# Valetudo.net
KiCad netlist of a schematic drawn in EAGLE
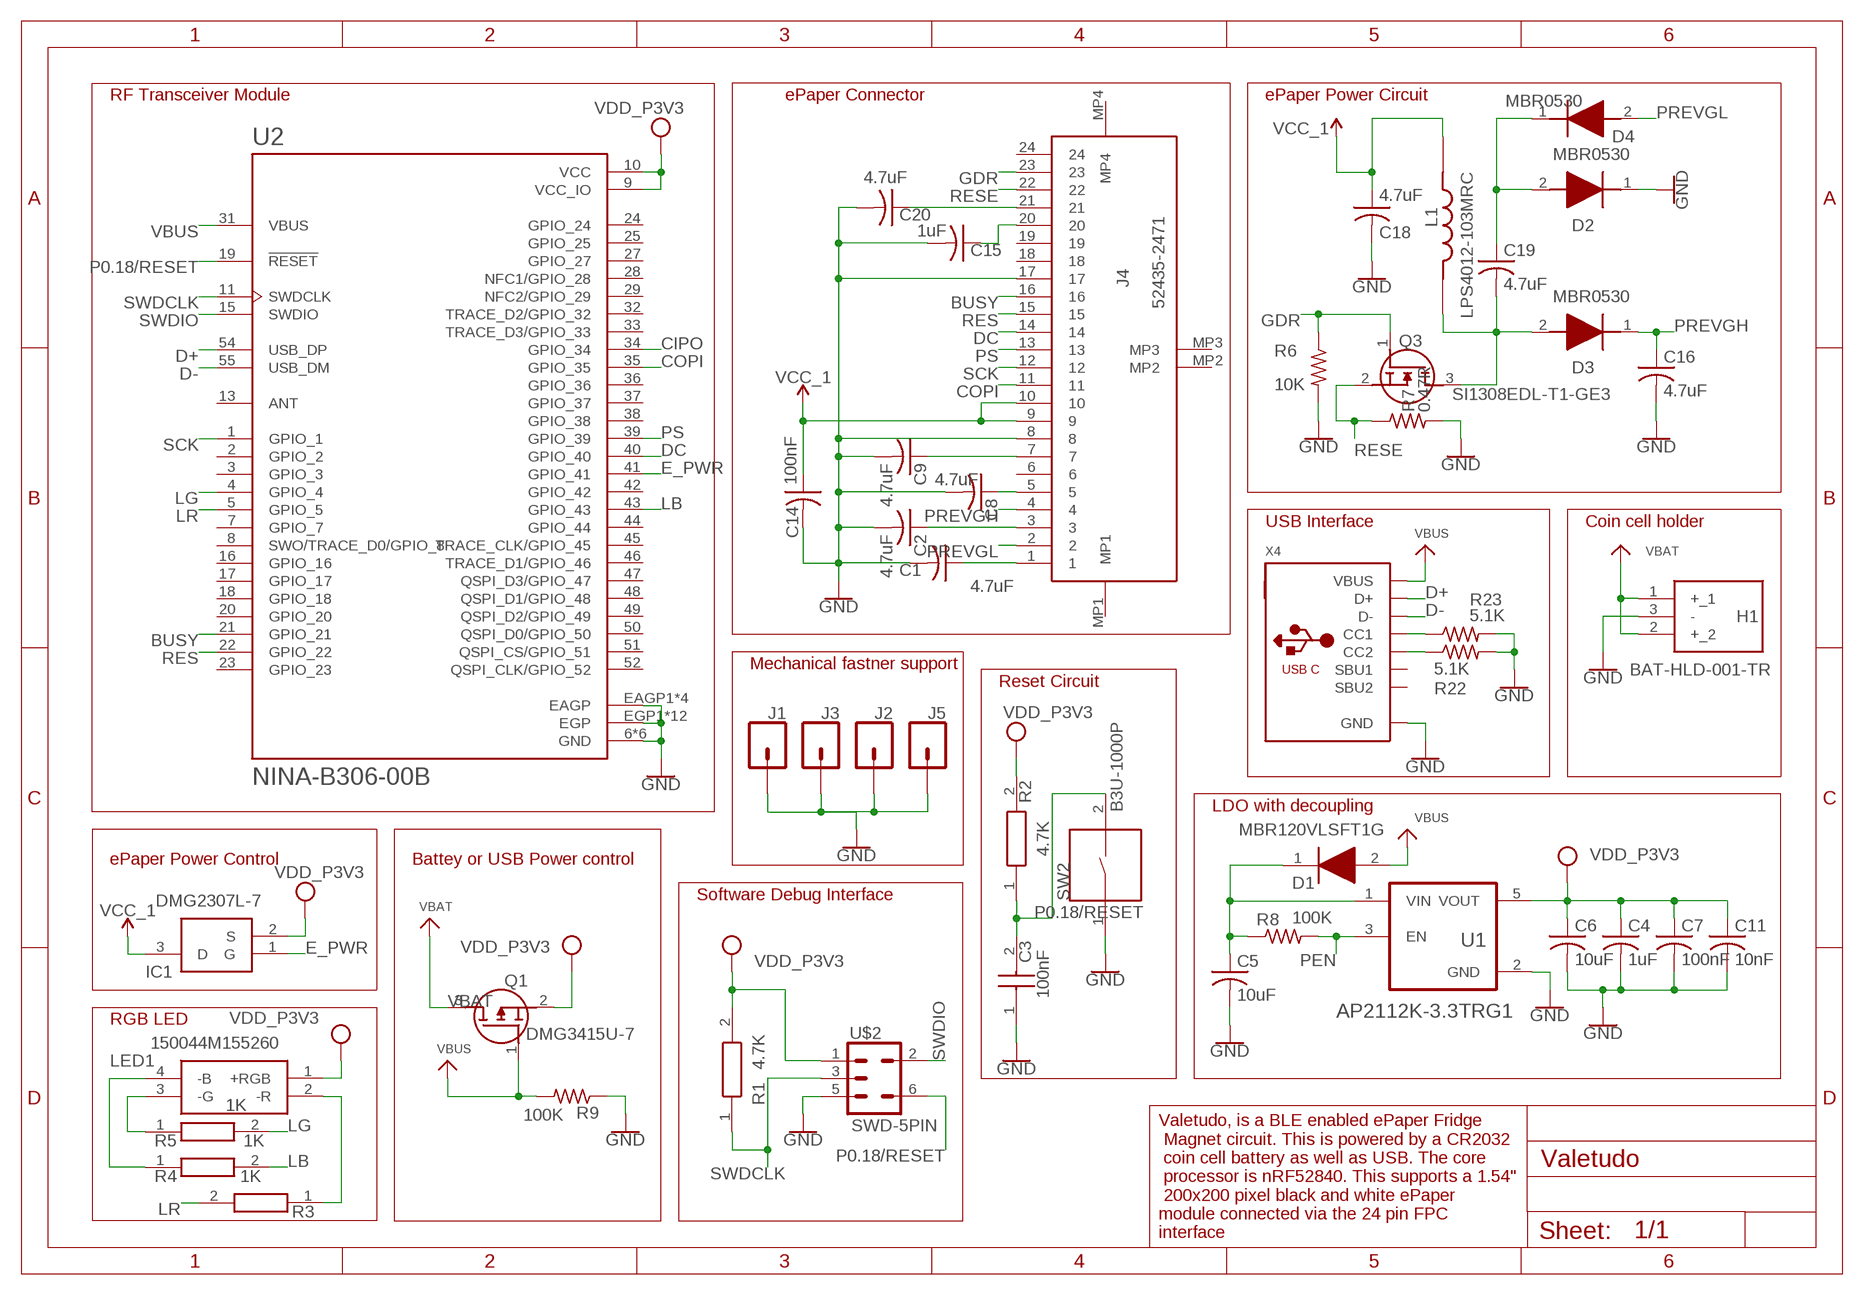
[diagram p0: schematic, sheet 1]

(export (version "E")
  (design (tool "Eeschema 10.0.6"))
  (components
    (comp (ref "C1")
      (value "4.7uF")
      (footprint "eagle-import:C0402")
      (libsource (lib "eagle-import") (part "C-USC0402"))
    )
    (comp (ref "C2")
      (value "4.7uF")
      (footprint "eagle-import:C0402")
      (libsource (lib "eagle-import") (part "C-USC0402"))
    )
    (comp (ref "C3")
      (value "100nF")
      (footprint "eagle-import:CAPC1005X55N")
      (fields
        (field (name "MANUFACTURER_PART_NUMBER") "GJM1555C1H120JB01J")
        (field (name "MOUSER_PART_NUMBER") "81-GJM1555C1H120JB1J")
      )
      (libsource (lib "eagle-import") (part "GJM1555C1H120JB01J"))
    )
    (comp (ref "C4")
      (value "1uF")
      (footprint "eagle-import:C0402")
      (libsource (lib "eagle-import") (part "C-USC0402"))
    )
    (comp (ref "C5")
      (value "10uF")
      (footprint "eagle-import:C0402")
      (libsource (lib "eagle-import") (part "C-USC0402"))
    )
    (comp (ref "C6")
      (value "10uF")
      (footprint "eagle-import:C0402")
      (libsource (lib "eagle-import") (part "C-USC0402"))
    )
    (comp (ref "C7")
      (value "100nF")
      (footprint "eagle-import:C0402")
      (libsource (lib "eagle-import") (part "C-USC0402"))
    )
    (comp (ref "C8")
      (value "4.7uF")
      (footprint "eagle-import:C0402")
      (libsource (lib "eagle-import") (part "C-USC0402"))
    )
    (comp (ref "C9")
      (value "4.7uF")
      (footprint "eagle-import:C0402")
      (libsource (lib "eagle-import") (part "C-USC0402"))
    )
    (comp (ref "C11")
      (value "10nF")
      (footprint "eagle-import:C0402")
      (libsource (lib "eagle-import") (part "C-USC0402"))
    )
    (comp (ref "C14")
      (value "100nF")
      (footprint "eagle-import:C0402")
      (libsource (lib "eagle-import") (part "C-USC0402"))
    )
    (comp (ref "C15")
      (value "1uF")
      (footprint "eagle-import:C0402")
      (libsource (lib "eagle-import") (part "C-USC0402"))
    )
    (comp (ref "C16")
      (value "4.7uF")
      (footprint "eagle-import:C0402")
      (libsource (lib "eagle-import") (part "C-USC0402"))
    )
    (comp (ref "C18")
      (value "4.7uF")
      (footprint "eagle-import:C0402")
      (libsource (lib "eagle-import") (part "C-USC0402"))
    )
    (comp (ref "C19")
      (value "4.7uF")
      (footprint "eagle-import:C0402")
      (libsource (lib "eagle-import") (part "C-USC0402"))
    )
    (comp (ref "C20")
      (value "4.7uF")
      (footprint "eagle-import:C0402")
      (libsource (lib "eagle-import") (part "C-USC0402"))
    )
    (comp (ref "D1")
      (value "MBR120VLSFT1G")
      (footprint "eagle-import:SODFL3616X98N")
      (fields (field (name "MOUSER_PART_NUMBER") "863-MBR120VLSFT1G"))
      (libsource (lib "eagle-import") (part "MBR120VLSFT1G"))
    )
    (comp (ref "D2")
      (value "MBR0530")
      (footprint "eagle-import:SOD3716X135N")
      (fields (field (name "MOUSER_PART_NUMBER") "512-MBR0530"))
      (libsource (lib "eagle-import") (part "MBR0530"))
    )
    (comp (ref "D3")
      (value "MBR0530")
      (footprint "eagle-import:SOD3716X135N")
      (fields (field (name "MOUSER_PART_NUMBER") "512-MBR0530"))
      (libsource (lib "eagle-import") (part "MBR0530"))
    )
    (comp (ref "D4")
      (value "MBR0530")
      (footprint "eagle-import:SOD3716X135N")
      (fields (field (name "MOUSER_PART_NUMBER") "512-MBR0530"))
      (libsource (lib "eagle-import") (part "MBR0530"))
    )
    (comp (ref "H1")
      (value "BAT-HLD-001-TR")
      (footprint "eagle-import:BATHLD001TR")
      (fields (field (name "MOUSER_PART_NUMBER") "712-BAT-HLD-001-TR"))
      (libsource (lib "eagle-import") (part "BAT-HLD-001-TR"))
    )
    (comp (ref "IC1")
      (value "DMG2307L-7")
      (footprint "eagle-import:SOT96P240X110-3N")
      (libsource (lib "eagle-import") (part "DMG2307L-7"))
    )
    (comp (ref "J1")
      (value "CONN_01PTH_2MM")
      (footprint "eagle-import:1X01_2MM")
      (libsource (lib "eagle-import") (part "CONN_01PTH_2MM"))
    )
    (comp (ref "J2")
      (value "CONN_01PTH_2MM")
      (footprint "eagle-import:1X01_2MM")
      (libsource (lib "eagle-import") (part "CONN_01PTH_2MM"))
    )
    (comp (ref "J3")
      (value "CONN_01PTH_2MM")
      (footprint "eagle-import:1X01_2MM")
      (libsource (lib "eagle-import") (part "CONN_01PTH_2MM"))
    )
    (comp (ref "J4")
      (value "52435-2471")
      (footprint "eagle-import:524352471")
      (fields (field (name "MOUSER_PART_NUMBER") "538-52435-2471"))
      (libsource (lib "eagle-import") (part "52435-2471"))
    )
    (comp (ref "J5")
      (value "CONN_01PTH_2MM")
      (footprint "eagle-import:1X01_2MM")
      (libsource (lib "eagle-import") (part "CONN_01PTH_2MM"))
    )
    (comp (ref "L1")
      (value "LPS4012-103MRC")
      (footprint "eagle-import:IND_LPS4012-103MRC")
      (fields (field (name "MF") "Coilcraft"))
      (libsource (lib "eagle-import") (part "LPS4012-103MRC"))
    )
    (comp (ref "LED1")
      (value "150044M155260")
      (footprint "eagle-import:150044M155260")
      (fields (field (name "MOUSER_PART_NUMBER") "710-150044M155260"))
      (libsource (lib "eagle-import") (part "150044M155260"))
    )
    (comp (ref "Q1")
      (value "DMG3415U-7")
      (footprint "eagle-import:SOT96P240X100-3N")
      (fields (field (name "LCSC_PART_NUMBER") "C96616"))
      (libsource (lib "eagle-import") (part "DMG3415U-7"))
    )
    (comp (ref "Q3")
      (value "SI1308EDL-T1-GE3")
      (footprint "eagle-import:SOT65P210X110-3N")
      (fields
        (field (name "MANUFACTURER_PART_NUMBER") "Si1308EDL-T1-GE3")
        (field (name "MOUSER_PART_NUMBER") "78-SI1308EDL-T1-GE3")
      )
      (libsource (lib "eagle-import") (part "SI1308EDL-T1-GE3"))
    )
    (comp (ref "R1")
      (value "4.7K")
      (footprint "eagle-import:RESC1005X40N")
      (fields
        (field (name "ARROW_PART_NUMBER") "CRCW04020000Z0EE")
        (field (name "MOUSER_PART_NUMBER") "71-CRCW04020000Z0EE")
      )
      (libsource (lib "eagle-import") (part "CRCW04020000Z0EE"))
    )
    (comp (ref "R2")
      (value "4.7K")
      (footprint "eagle-import:RESC1005X40N")
      (fields
        (field (name "ARROW_PART_NUMBER") "CRCW04020000Z0EE")
        (field (name "MOUSER_PART_NUMBER") "71-CRCW04020000Z0EE")
      )
      (libsource (lib "eagle-import") (part "CRCW04020000Z0EE"))
    )
    (comp (ref "R3")
      (value "1K")
      (footprint "eagle-import:RESC1005X40N")
      (fields
        (field (name "ARROW_PART_NUMBER") "CRCW04020000Z0EE")
        (field (name "MOUSER_PART_NUMBER") "71-CRCW04020000Z0EE")
      )
      (libsource (lib "eagle-import") (part "CRCW04020000Z0EE"))
    )
    (comp (ref "R4")
      (value "1K")
      (footprint "eagle-import:RESC1005X40N")
      (fields
        (field (name "ARROW_PART_NUMBER") "CRCW04020000Z0EE")
        (field (name "MOUSER_PART_NUMBER") "71-CRCW04020000Z0EE")
      )
      (libsource (lib "eagle-import") (part "CRCW04020000Z0EE"))
    )
    (comp (ref "R5")
      (value "1K")
      (footprint "eagle-import:RESC1005X40N")
      (fields
        (field (name "ARROW_PART_NUMBER") "CRCW04020000Z0EE")
        (field (name "MOUSER_PART_NUMBER") "71-CRCW04020000Z0EE")
      )
      (libsource (lib "eagle-import") (part "CRCW04020000Z0EE"))
    )
    (comp (ref "R6")
      (value "10K")
      (footprint "eagle-import:R0402")
      (libsource (lib "eagle-import") (part "R-US_R0402"))
    )
    (comp (ref "R7")
      (value "0.47R")
      (footprint "eagle-import:R0402")
      (libsource (lib "eagle-import") (part "R-US_R0402"))
    )
    (comp (ref "R8")
      (value "100K")
      (footprint "eagle-import:R0402")
      (libsource (lib "eagle-import") (part "R-US_R0402"))
    )
    (comp (ref "R9")
      (value "100K")
      (footprint "eagle-import:R0402")
      (libsource (lib "eagle-import") (part "R-US_R0402"))
    )
    (comp (ref "R22")
      (value "5.1K")
      (footprint "eagle-import:R0402")
      (libsource (lib "eagle-import") (part "R-US_R0402"))
    )
    (comp (ref "R23")
      (value "5.1K")
      (footprint "eagle-import:R0402")
      (libsource (lib "eagle-import") (part "R-US_R0402"))
    )
    (comp (ref "SW2")
      (value "B3U-1000P")
      (footprint "eagle-import:SW_B3U-1000P")
      (fields (field (name "MF") "Omron"))
      (libsource (lib "eagle-import") (part "B3U-1000P"))
    )
    (comp (ref "U$2")
      (value "SWD-5PIN")
      (footprint "eagle-import:PAD_05_03X2_TP_NO4")
      (libsource (lib "eagle-import") (part "SWD-5PIN"))
    )
    (comp (ref "U1")
      (value "AP2112K-3.3TRG1")
      (footprint "eagle-import:SOT95P285X140-5N")
      (fields (field (name "MF") "Diodes Inc."))
      (libsource (lib "eagle-import") (part "AP2112K-3.3TRG1"))
    )
    (comp (ref "U2")
      (value "NINA-B306-00B")
      (footprint "eagle-import:XCVR_NINA-B306-00B")
      (fields (field (name "MF") "U-Blox"))
      (libsource (lib "eagle-import") (part "NINA-B306-00B"))
    )
    (comp (ref "X4")
      (value "MICROBUILDER_USB_C")
      (footprint "eagle-import:MICROBUILDER_USB_C_CUSB31-CFM2AX-01-X")
      (libsource (lib "eagle-import") (part "MICROBUILDER_USB_C"))
    )
  )
  (nets
    (net (code "1") (name "/BUSY") (class "Default")
      (node (ref "J4") (pin "16") (pinfunction "16_16") (pintype "bidirectional"))
      (node (ref "U2") (pin "21") (pinfunction "GPIO_21_21") (pintype "bidirectional"))
    )
    (net (code "2") (name "/CIPO") (class "Default")
      (node (ref "U2") (pin "34") (pinfunction "GPIO_34_34") (pintype "bidirectional"))
    )
    (net (code "3") (name "/COPI") (class "Default")
      (node (ref "J4") (pin "11") (pinfunction "11_11") (pintype "bidirectional"))
      (node (ref "U2") (pin "35") (pinfunction "GPIO_35_35") (pintype "bidirectional"))
    )
    (net (code "4") (name "/D+") (class "Default")
      (node (ref "U2") (pin "54") (pinfunction "USB_DP_54") (pintype "bidirectional"))
      (node (ref "X4") (pin "A6") (pinfunction "D+_A6") (pintype "bidirectional"))
      (node (ref "X4") (pin "B6") (pinfunction "D+_B6") (pintype "bidirectional"))
    )
    (net (code "5") (name "/D-") (class "Default")
      (node (ref "U2") (pin "55") (pinfunction "USB_DM_55") (pintype "bidirectional"))
      (node (ref "X4") (pin "A7") (pinfunction "D-_A7") (pintype "bidirectional"))
      (node (ref "X4") (pin "B7") (pinfunction "D-_B7") (pintype "bidirectional"))
    )
    (net (code "6") (name "/DC") (class "Default")
      (node (ref "J4") (pin "14") (pinfunction "14_14") (pintype "bidirectional"))
      (node (ref "U2") (pin "40") (pinfunction "GPIO_40_40") (pintype "bidirectional"))
    )
    (net (code "7") (name "/E_PWR") (class "Default")
      (node (ref "IC1") (pin "1") (pinfunction "G_1") (pintype "bidirectional"))
      (node (ref "U2") (pin "41") (pinfunction "GPIO_41_41") (pintype "bidirectional"))
    )
    (net (code "8") (name "/GDR") (class "Default")
      (node (ref "J4") (pin "23") (pinfunction "23_23") (pintype "bidirectional"))
      (node (ref "Q3") (pin "1") (pinfunction "G_1") (pintype "bidirectional"))
      (node (ref "R6") (pin "1") (pinfunction "1_1") (pintype "passive"))
    )
    (net (code "9") (name "/LB") (class "Default")
      (node (ref "R4") (pin "2") (pinfunction "2_2") (pintype "bidirectional"))
      (node (ref "U2") (pin "43") (pinfunction "GPIO_43_43") (pintype "bidirectional"))
    )
    (net (code "10") (name "/LG") (class "Default")
      (node (ref "R5") (pin "2") (pinfunction "2_2") (pintype "bidirectional"))
      (node (ref "U2") (pin "4") (pinfunction "GPIO_4_4") (pintype "bidirectional"))
    )
    (net (code "11") (name "/LR") (class "Default")
      (node (ref "R3") (pin "2") (pinfunction "2_2") (pintype "bidirectional"))
      (node (ref "U2") (pin "5") (pinfunction "GPIO_5_5") (pintype "bidirectional"))
    )
    (net (code "12") (name "/P0.18{slash}RESET") (class "Default")
      (node (ref "C3") (pin "2") (pinfunction "2_2") (pintype "bidirectional"))
      (node (ref "R2") (pin "1") (pinfunction "1_1") (pintype "bidirectional"))
      (node (ref "SW2") (pin "2") (pinfunction "2_2") (pintype "passive"))
      (node (ref "U$2") (pin "6") (pinfunction "6_6") (pintype "bidirectional"))
      (node (ref "U2") (pin "19") (pinfunction "~{RESET}_19") (pintype "bidirectional"))
    )
    (net (code "13") (name "/PEN") (class "Default")
      (node (ref "R8") (pin "2") (pinfunction "2_2") (pintype "passive"))
      (node (ref "U1") (pin "3") (pinfunction "EN_3") (pintype "input"))
    )
    (net (code "14") (name "/PREVGH") (class "Default")
      (node (ref "C16") (pin "1") (pinfunction "1_1") (pintype "passive"))
      (node (ref "D3") (pin "1") (pinfunction "K_1") (pintype "bidirectional"))
      (node (ref "J4") (pin "4") (pinfunction "4_4") (pintype "bidirectional"))
    )
    (net (code "15") (name "/PREVGL") (class "Default")
      (node (ref "D4") (pin "2") (pinfunction "A_2") (pintype "bidirectional"))
      (node (ref "J4") (pin "2") (pinfunction "2_2") (pintype "bidirectional"))
    )
    (net (code "16") (name "/PS") (class "Default")
      (node (ref "J4") (pin "13") (pinfunction "13_13") (pintype "bidirectional"))
      (node (ref "U2") (pin "39") (pinfunction "GPIO_39_39") (pintype "bidirectional"))
    )
    (net (code "17") (name "/RES") (class "Default")
      (node (ref "J4") (pin "15") (pinfunction "15_15") (pintype "bidirectional"))
      (node (ref "U2") (pin "22") (pinfunction "GPIO_22_22") (pintype "bidirectional"))
    )
    (net (code "18") (name "/RESE") (class "Default")
      (node (ref "J4") (pin "22") (pinfunction "22_22") (pintype "bidirectional"))
      (node (ref "Q3") (pin "2") (pinfunction "S_2") (pintype "bidirectional"))
      (node (ref "R7") (pin "1") (pinfunction "1_1") (pintype "passive"))
    )
    (net (code "19") (name "/SCK") (class "Default")
      (node (ref "J4") (pin "12") (pinfunction "12_12") (pintype "bidirectional"))
      (node (ref "U2") (pin "1") (pinfunction "GPIO_1_1") (pintype "bidirectional"))
    )
    (net (code "20") (name "/SWDCLK") (class "Default")
      (node (ref "R1") (pin "1") (pinfunction "1_1") (pintype "bidirectional"))
      (node (ref "U$2") (pin "3") (pinfunction "3_3") (pintype "bidirectional"))
      (node (ref "U2") (pin "11") (pinfunction "SWDCLK_11") (pintype "input"))
    )
    (net (code "21") (name "/SWDIO") (class "Default")
      (node (ref "U$2") (pin "2") (pinfunction "2_2") (pintype "bidirectional"))
      (node (ref "U2") (pin "15") (pinfunction "SWDIO_15") (pintype "bidirectional"))
    )
    (net (code "22") (name "GND") (class "Default")
      (node (ref "C1") (pin "2") (pinfunction "2_2") (pintype "passive"))
      (node (ref "C11") (pin "2") (pinfunction "2_2") (pintype "passive"))
      (node (ref "C14") (pin "2") (pinfunction "2_2") (pintype "passive"))
      (node (ref "C15") (pin "2") (pinfunction "2_2") (pintype "passive"))
      (node (ref "C16") (pin "2") (pinfunction "2_2") (pintype "passive"))
      (node (ref "C18") (pin "2") (pinfunction "2_2") (pintype "passive"))
      (node (ref "C2") (pin "2") (pinfunction "2_2") (pintype "passive"))
      (node (ref "C20") (pin "2") (pinfunction "2_2") (pintype "passive"))
      (node (ref "C3") (pin "1") (pinfunction "1_1") (pintype "bidirectional"))
      (node (ref "C4") (pin "2") (pinfunction "2_2") (pintype "passive"))
      (node (ref "C5") (pin "2") (pinfunction "2_2") (pintype "passive"))
      (node (ref "C6") (pin "2") (pinfunction "2_2") (pintype "passive"))
      (node (ref "C7") (pin "2") (pinfunction "2_2") (pintype "passive"))
      (node (ref "C8") (pin "2") (pinfunction "2_2") (pintype "passive"))
      (node (ref "C9") (pin "2") (pinfunction "2_2") (pintype "passive"))
      (node (ref "D2") (pin "1") (pinfunction "K_1") (pintype "bidirectional"))
      (node (ref "H1") (pin "3") (pinfunction "-_3") (pintype "bidirectional"))
      (node (ref "J1") (pin "1") (pinfunction "1_1") (pintype "passive"))
      (node (ref "J2") (pin "1") (pinfunction "1_1") (pintype "passive"))
      (node (ref "J3") (pin "1") (pinfunction "1_1") (pintype "passive"))
      (node (ref "J4") (pin "17") (pinfunction "17_17") (pintype "bidirectional"))
      (node (ref "J4") (pin "8") (pinfunction "8_8") (pintype "bidirectional"))
      (node (ref "J5") (pin "1") (pinfunction "1_1") (pintype "passive"))
      (node (ref "R22") (pin "2") (pinfunction "2_2") (pintype "passive"))
      (node (ref "R23") (pin "2") (pinfunction "2_2") (pintype "passive"))
      (node (ref "R6") (pin "2") (pinfunction "2_2") (pintype "passive"))
      (node (ref "R7") (pin "2") (pinfunction "2_2") (pintype "passive"))
      (node (ref "R9") (pin "1") (pinfunction "1_1") (pintype "passive"))
      (node (ref "SW2") (pin "1") (pinfunction "1_1") (pintype "passive"))
      (node (ref "U$2") (pin "5") (pinfunction "5_5") (pintype "bidirectional"))
      (node (ref "U1") (pin "2") (pinfunction "GND_2") (pintype "power_in"))
      (node (ref "U2") (pin "12") (pinfunction "GND_12") (pintype "power_in"))
      (node (ref "U2") (pin "14") (pinfunction "GND_14") (pintype "power_in"))
      (node (ref "U2") (pin "26") (pinfunction "GND_26") (pintype "power_in"))
      (node (ref "U2") (pin "30") (pinfunction "GND_30") (pintype "power_in"))
      (node (ref "U2") (pin "53") (pinfunction "GND_53") (pintype "power_in"))
      (node (ref "U2") (pin "6") (pinfunction "GND_6") (pintype "power_in"))
      (node (ref "U2") (pin "EAGP1") (pinfunction "EAGP_EAGP1") (pintype "power_in"))
      (node (ref "U2") (pin "EAGP2") (pinfunction "EAGP_EAGP2") (pintype "power_in"))
      (node (ref "U2") (pin "EAGP3") (pinfunction "EAGP_EAGP3") (pintype "power_in"))
      (node (ref "U2") (pin "EAGP4") (pinfunction "EAGP_EAGP4") (pintype "power_in"))
      (node (ref "U2") (pin "EGP1") (pinfunction "EGP_EGP1") (pintype "power_in"))
      (node (ref "U2") (pin "EGP10") (pinfunction "EGP_EGP10") (pintype "power_in"))
      (node (ref "U2") (pin "EGP11") (pinfunction "EGP_EGP11") (pintype "power_in"))
      (node (ref "U2") (pin "EGP12") (pinfunction "EGP_EGP12") (pintype "power_in"))
      (node (ref "U2") (pin "EGP2") (pinfunction "EGP_EGP2") (pintype "power_in"))
      (node (ref "U2") (pin "EGP3") (pinfunction "EGP_EGP3") (pintype "power_in"))
      (node (ref "U2") (pin "EGP4") (pinfunction "EGP_EGP4") (pintype "power_in"))
      (node (ref "U2") (pin "EGP5") (pinfunction "EGP_EGP5") (pintype "power_in"))
      (node (ref "U2") (pin "EGP6") (pinfunction "EGP_EGP6") (pintype "power_in"))
      (node (ref "U2") (pin "EGP7") (pinfunction "EGP_EGP7") (pintype "power_in"))
      (node (ref "U2") (pin "EGP8") (pinfunction "EGP_EGP8") (pintype "power_in"))
      (node (ref "U2") (pin "EGP9") (pinfunction "EGP_EGP9") (pintype "power_in"))
      (node (ref "X4") (pin "A1B12") (pinfunction "GND_A1B12") (pintype "power_in"))
      (node (ref "X4") (pin "B1A12") (pinfunction "GND_B1A12") (pintype "power_in"))
    )
    (net (code "23") (name "Net-(C1-Pad1)") (class "Default")
      (node (ref "C1") (pin "1") (pinfunction "1_1") (pintype "passive"))
      (node (ref "J4") (pin "1") (pinfunction "1_1") (pintype "bidirectional"))
    )
    (net (code "24") (name "Net-(C2-Pad1)") (class "Default")
      (node (ref "C2") (pin "1") (pinfunction "1_1") (pintype "passive"))
      (node (ref "J4") (pin "3") (pinfunction "3_3") (pintype "bidirectional"))
    )
    (net (code "25") (name "Net-(C8-Pad1)") (class "Default")
      (node (ref "C8") (pin "1") (pinfunction "1_1") (pintype "passive"))
      (node (ref "J4") (pin "5") (pinfunction "5_5") (pintype "bidirectional"))
    )
    (net (code "26") (name "Net-(C9-Pad1)") (class "Default")
      (node (ref "C9") (pin "1") (pinfunction "1_1") (pintype "passive"))
      (node (ref "J4") (pin "7") (pinfunction "7_7") (pintype "bidirectional"))
    )
    (net (code "27") (name "Net-(C15-Pad1)") (class "Default")
      (node (ref "C15") (pin "1") (pinfunction "1_1") (pintype "passive"))
      (node (ref "J4") (pin "20") (pinfunction "20_20") (pintype "bidirectional"))
    )
    (net (code "28") (name "Net-(C20-Pad1)") (class "Default")
      (node (ref "C20") (pin "1") (pinfunction "1_1") (pintype "passive"))
      (node (ref "J4") (pin "21") (pinfunction "21_21") (pintype "bidirectional"))
    )
    (net (code "29") (name "Net-(D1-K)") (class "Default")
      (node (ref "C5") (pin "1") (pinfunction "1_1") (pintype "passive"))
      (node (ref "D1") (pin "1") (pinfunction "K_1") (pintype "bidirectional"))
      (node (ref "R8") (pin "1") (pinfunction "1_1") (pintype "passive"))
      (node (ref "U1") (pin "1") (pinfunction "VIN_1") (pintype "power_in"))
    )
    (net (code "30") (name "Net-(D2-A)") (class "Default")
      (node (ref "C19") (pin "1") (pinfunction "1_1") (pintype "passive"))
      (node (ref "D2") (pin "2") (pinfunction "A_2") (pintype "bidirectional"))
      (node (ref "D4") (pin "1") (pinfunction "K_1") (pintype "bidirectional"))
    )
    (net (code "31") (name "Net-(D3-A)") (class "Default")
      (node (ref "C19") (pin "2") (pinfunction "2_2") (pintype "passive"))
      (node (ref "D3") (pin "2") (pinfunction "A_2") (pintype "bidirectional"))
      (node (ref "L1") (pin "2") (pinfunction "2_2") (pintype "passive"))
      (node (ref "Q3") (pin "3") (pinfunction "D_3") (pintype "bidirectional"))
    )
    (net (code "32") (name "Net-(LED1--B)") (class "Default")
      (node (ref "LED1") (pin "4") (pinfunction "-B_4") (pintype "bidirectional"))
      (node (ref "R4") (pin "1") (pinfunction "1_1") (pintype "bidirectional"))
    )
    (net (code "33") (name "Net-(LED1--G)") (class "Default")
      (node (ref "LED1") (pin "3") (pinfunction "-G_3") (pintype "bidirectional"))
      (node (ref "R5") (pin "1") (pinfunction "1_1") (pintype "bidirectional"))
    )
    (net (code "34") (name "Net-(LED1--R)") (class "Default")
      (node (ref "LED1") (pin "2") (pinfunction "-R_2") (pintype "bidirectional"))
      (node (ref "R3") (pin "1") (pinfunction "1_1") (pintype "bidirectional"))
    )
    (net (code "35") (name "Net-(X4-CC1)") (class "Default")
      (node (ref "R23") (pin "1") (pinfunction "1_1") (pintype "passive"))
      (node (ref "X4") (pin "A5") (pinfunction "CC1_A5") (pintype "bidirectional"))
    )
    (net (code "36") (name "Net-(X4-CC2)") (class "Default")
      (node (ref "R22") (pin "1") (pinfunction "1_1") (pintype "passive"))
      (node (ref "X4") (pin "B5") (pinfunction "CC2_B5") (pintype "bidirectional"))
    )
    (net (code "37") (name "VBAT") (class "Default")
      (node (ref "H1") (pin "1") (pinfunction "+_1_1") (pintype "bidirectional"))
      (node (ref "H1") (pin "2") (pinfunction "+_2_2") (pintype "bidirectional"))
      (node (ref "Q1") (pin "3") (pinfunction "D_3") (pintype "bidirectional"))
    )
    (net (code "38") (name "VBUS") (class "Default")
      (node (ref "D1") (pin "2") (pinfunction "A_2") (pintype "bidirectional"))
      (node (ref "Q1") (pin "1") (pinfunction "G_1") (pintype "bidirectional"))
      (node (ref "R9") (pin "2") (pinfunction "2_2") (pintype "passive"))
      (node (ref "U2") (pin "31") (pinfunction "VBUS_31") (pintype "input"))
      (node (ref "X4") (pin "A4B9") (pinfunction "VBUS_A4B9") (pintype "power_in"))
      (node (ref "X4") (pin "B4A9") (pinfunction "VBUS_B4A9") (pintype "power_in"))
    )
    (net (code "39") (name "VCC_1") (class "Default")
      (node (ref "C14") (pin "1") (pinfunction "1_1") (pintype "passive"))
      (node (ref "C18") (pin "1") (pinfunction "1_1") (pintype "passive"))
      (node (ref "IC1") (pin "3") (pinfunction "D_3") (pintype "bidirectional"))
      (node (ref "J4") (pin "10") (pinfunction "10_10") (pintype "bidirectional"))
      (node (ref "J4") (pin "9") (pinfunction "9_9") (pintype "bidirectional"))
      (node (ref "L1") (pin "1") (pinfunction "1_1") (pintype "passive"))
    )
    (net (code "40") (name "VDD_P3V3") (class "Default")
      (node (ref "C11") (pin "1") (pinfunction "1_1") (pintype "passive"))
      (node (ref "C4") (pin "1") (pinfunction "1_1") (pintype "passive"))
      (node (ref "C6") (pin "1") (pinfunction "1_1") (pintype "passive"))
      (node (ref "C7") (pin "1") (pinfunction "1_1") (pintype "passive"))
      (node (ref "IC1") (pin "2") (pinfunction "S_2") (pintype "bidirectional"))
      (node (ref "LED1") (pin "1") (pinfunction "+RGB_1") (pintype "bidirectional"))
      (node (ref "Q1") (pin "2") (pinfunction "S_2") (pintype "bidirectional"))
      (node (ref "R1") (pin "2") (pinfunction "2_2") (pintype "bidirectional"))
      (node (ref "R2") (pin "2") (pinfunction "2_2") (pintype "bidirectional"))
      (node (ref "U$2") (pin "1") (pinfunction "1_1") (pintype "bidirectional"))
      (node (ref "U1") (pin "5") (pinfunction "VOUT_5") (pintype "power_in"))
      (node (ref "U2") (pin "10") (pinfunction "VCC_10") (pintype "power_in"))
      (node (ref "U2") (pin "9") (pinfunction "VCC_IO_9") (pintype "power_in"))
    )
    (net (code "41") (name "unconnected-(J4-Pad6)") (class "Default")
      (node (ref "J4") (pin "6") (pinfunction "6_6") (pintype "bidirectional"))
    )
    (net (code "42") (name "unconnected-(J4-Pad18)") (class "Default")
      (node (ref "J4") (pin "18") (pinfunction "18_18") (pintype "bidirectional"))
    )
    (net (code "43") (name "unconnected-(J4-Pad19)") (class "Default")
      (node (ref "J4") (pin "19") (pinfunction "19_19") (pintype "bidirectional"))
    )
    (net (code "44") (name "unconnected-(J4-Pad24)") (class "Default")
      (node (ref "J4") (pin "24") (pinfunction "24_24") (pintype "bidirectional"))
    )
    (net (code "45") (name "unconnected-(J4-PadMP1)") (class "Default")
      (node (ref "J4") (pin "MP1") (pinfunction "MP1_MP1") (pintype "bidirectional"))
    )
    (net (code "46") (name "unconnected-(J4-PadMP2)") (class "Default")
      (node (ref "J4") (pin "MP2") (pinfunction "MP2_MP2") (pintype "bidirectional"))
    )
    (net (code "47") (name "unconnected-(J4-PadMP3)") (class "Default")
      (node (ref "J4") (pin "MP3") (pinfunction "MP3_MP3") (pintype "bidirectional"))
    )
    (net (code "48") (name "unconnected-(J4-PadMP4)") (class "Default")
      (node (ref "J4") (pin "MP4") (pinfunction "MP4_MP4") (pintype "bidirectional"))
    )
    (net (code "49") (name "unconnected-(U2-ANT-Pad13)") (class "Default")
      (node (ref "U2") (pin "13") (pinfunction "ANT_13") (pintype "bidirectional"))
    )
    (net (code "50") (name "unconnected-(U2-GPIO_2-Pad2)") (class "Default")
      (node (ref "U2") (pin "2") (pinfunction "GPIO_2_2") (pintype "bidirectional"))
    )
    (net (code "51") (name "unconnected-(U2-GPIO_3-Pad3)") (class "Default")
      (node (ref "U2") (pin "3") (pinfunction "GPIO_3_3") (pintype "bidirectional"))
    )
    (net (code "52") (name "unconnected-(U2-GPIO_7-Pad7)") (class "Default")
      (node (ref "U2") (pin "7") (pinfunction "GPIO_7_7") (pintype "bidirectional"))
    )
    (net (code "53") (name "unconnected-(U2-GPIO_16-Pad16)") (class "Default")
      (node (ref "U2") (pin "16") (pinfunction "GPIO_16_16") (pintype "bidirectional"))
    )
    (net (code "54") (name "unconnected-(U2-GPIO_17-Pad17)") (class "Default")
      (node (ref "U2") (pin "17") (pinfunction "GPIO_17_17") (pintype "bidirectional"))
    )
    (net (code "55") (name "unconnected-(U2-GPIO_18-Pad18)") (class "Default")
      (node (ref "U2") (pin "18") (pinfunction "GPIO_18_18") (pintype "bidirectional"))
    )
    (net (code "56") (name "unconnected-(U2-GPIO_20-Pad20)") (class "Default")
      (node (ref "U2") (pin "20") (pinfunction "GPIO_20_20") (pintype "bidirectional"))
    )
    (net (code "57") (name "unconnected-(U2-GPIO_23-Pad23)") (class "Default")
      (node (ref "U2") (pin "23") (pinfunction "GPIO_23_23") (pintype "bidirectional"))
    )
    (net (code "58") (name "unconnected-(U2-GPIO_24-Pad24)") (class "Default")
      (node (ref "U2") (pin "24") (pinfunction "GPIO_24_24") (pintype "bidirectional"))
    )
    (net (code "59") (name "unconnected-(U2-GPIO_25-Pad25)") (class "Default")
      (node (ref "U2") (pin "25") (pinfunction "GPIO_25_25") (pintype "bidirectional"))
    )
    (net (code "60") (name "unconnected-(U2-GPIO_27-Pad27)") (class "Default")
      (node (ref "U2") (pin "27") (pinfunction "GPIO_27_27") (pintype "bidirectional"))
    )
    (net (code "61") (name "unconnected-(U2-GPIO_36-Pad36)") (class "Default")
      (node (ref "U2") (pin "36") (pinfunction "GPIO_36_36") (pintype "bidirectional"))
    )
    (net (code "62") (name "unconnected-(U2-GPIO_37-Pad37)") (class "Default")
      (node (ref "U2") (pin "37") (pinfunction "GPIO_37_37") (pintype "bidirectional"))
    )
    (net (code "63") (name "unconnected-(U2-GPIO_38-Pad38)") (class "Default")
      (node (ref "U2") (pin "38") (pinfunction "GPIO_38_38") (pintype "bidirectional"))
    )
    (net (code "64") (name "unconnected-(U2-GPIO_42-Pad42)") (class "Default")
      (node (ref "U2") (pin "42") (pinfunction "GPIO_42_42") (pintype "bidirectional"))
    )
    (net (code "65") (name "unconnected-(U2-GPIO_44-Pad44)") (class "Default")
      (node (ref "U2") (pin "44") (pinfunction "GPIO_44_44") (pintype "bidirectional"))
    )
    (net (code "66") (name "unconnected-(U2-NFC1{slash}GPIO_28-Pad28)") (class "Default")
      (node (ref "U2") (pin "28") (pinfunction "NFC1/GPIO_28_28") (pintype "bidirectional"))
    )
    (net (code "67") (name "unconnected-(U2-NFC2{slash}GPIO_29-Pad29)") (class "Default")
      (node (ref "U2") (pin "29") (pinfunction "NFC2/GPIO_29_29") (pintype "bidirectional"))
    )
    (net (code "68") (name "unconnected-(U2-QSPI_CLK{slash}GPIO_52-Pad52)") (class "Default")
      (node (ref "U2") (pin "52") (pinfunction "QSPI_CLK/GPIO_52_52") (pintype "bidirectional"))
    )
    (net (code "69") (name "unconnected-(U2-QSPI_CS{slash}GPIO_51-Pad51)") (class "Default")
      (node (ref "U2") (pin "51") (pinfunction "QSPI_CS/GPIO_51_51") (pintype "bidirectional"))
    )
    (net (code "70") (name "unconnected-(U2-QSPI_D0{slash}GPIO_50-Pad50)") (class "Default")
      (node (ref "U2") (pin "50") (pinfunction "QSPI_D0/GPIO_50_50") (pintype "bidirectional"))
    )
    (net (code "71") (name "unconnected-(U2-QSPI_D1{slash}GPIO_48-Pad48)") (class "Default")
      (node (ref "U2") (pin "48") (pinfunction "QSPI_D1/GPIO_48_48") (pintype "bidirectional"))
    )
    (net (code "72") (name "unconnected-(U2-QSPI_D2{slash}GPIO_49-Pad49)") (class "Default")
      (node (ref "U2") (pin "49") (pinfunction "QSPI_D2/GPIO_49_49") (pintype "bidirectional"))
    )
    (net (code "73") (name "unconnected-(U2-QSPI_D3{slash}GPIO_47-Pad47)") (class "Default")
      (node (ref "U2") (pin "47") (pinfunction "QSPI_D3/GPIO_47_47") (pintype "bidirectional"))
    )
    (net (code "74") (name "unconnected-(U2-SWO{slash}TRACE_D0{slash}GPIO_8-Pad8)") (class "Default")
      (node (ref "U2") (pin "8") (pinfunction "SWO/TRACE_D0/GPIO_8_8") (pintype "bidirectional"))
    )
    (net (code "75") (name "unconnected-(U2-TRACE_CLK{slash}GPIO_45-Pad45)") (class "Default")
      (node (ref "U2") (pin "45") (pinfunction "TRACE_CLK/GPIO_45_45") (pintype "bidirectional"))
    )
    (net (code "76") (name "unconnected-(U2-TRACE_D1{slash}GPIO_46-Pad46)") (class "Default")
      (node (ref "U2") (pin "46") (pinfunction "TRACE_D1/GPIO_46_46") (pintype "bidirectional"))
    )
    (net (code "77") (name "unconnected-(U2-TRACE_D2{slash}GPIO_32-Pad32)") (class "Default")
      (node (ref "U2") (pin "32") (pinfunction "TRACE_D2/GPIO_32_32") (pintype "bidirectional"))
    )
    (net (code "78") (name "unconnected-(U2-TRACE_D3{slash}GPIO_33-Pad33)") (class "Default")
      (node (ref "U2") (pin "33") (pinfunction "TRACE_D3/GPIO_33_33") (pintype "bidirectional"))
    )
    (net (code "79") (name "unconnected-(X4-SBU1-PadA8)") (class "Default")
      (node (ref "X4") (pin "A8") (pinfunction "SBU1_A8") (pintype "bidirectional"))
    )
    (net (code "80") (name "unconnected-(X4-SBU2-PadB8)") (class "Default")
      (node (ref "X4") (pin "B8") (pinfunction "SBU2_B8") (pintype "bidirectional"))
    )
  )
)
